# mod_mixer_no_led.net
KiCad netlist of a schematic drawn in EAGLE
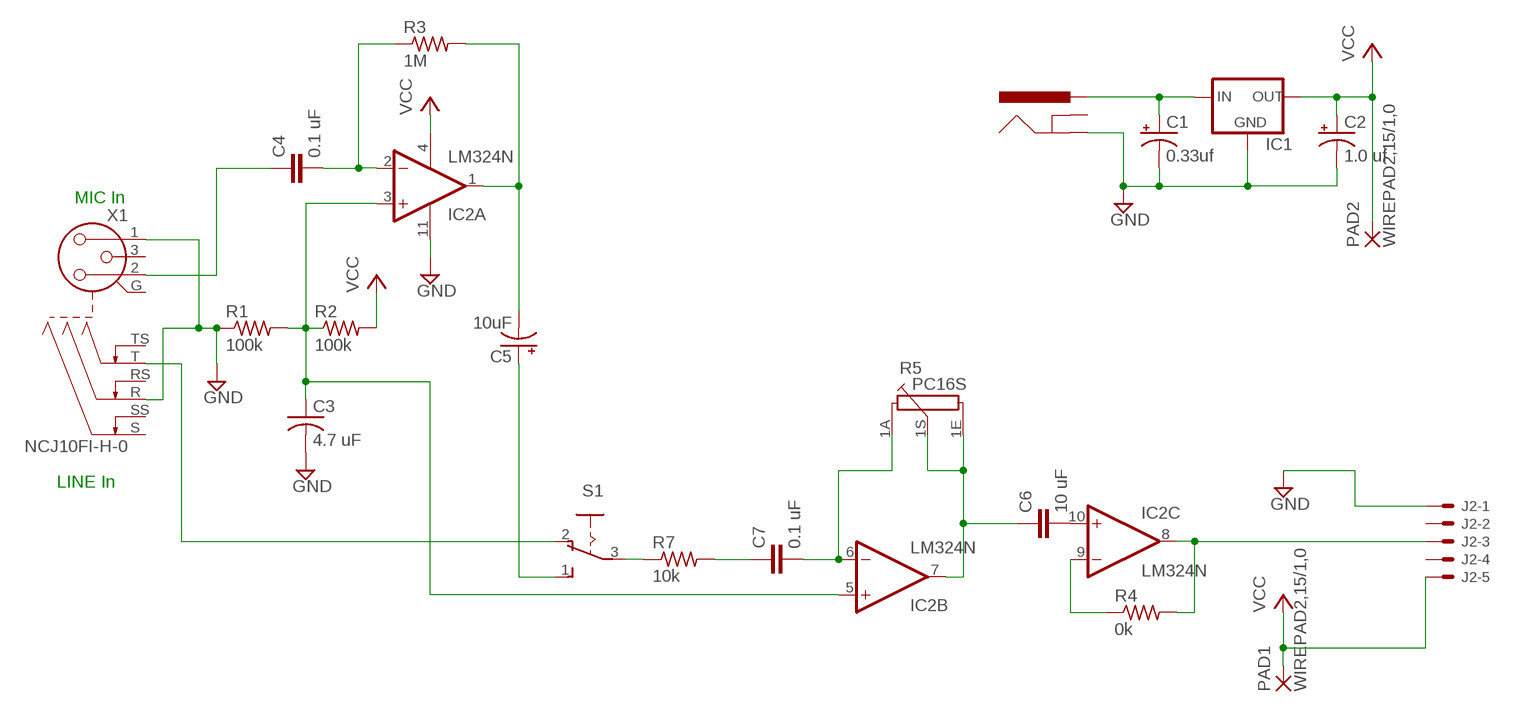
[diagram p0: schematic, sheet 1]

(export (version "E")
  (design (tool "Eeschema 10.0.6"))
  (components
    (comp (ref "C1")
      (value "0.33uf")
      (footprint "eagle-import:E2,5-6")
      (libsource (lib "eagle-import") (part "CPOL-USE2.5-6"))
    )
    (comp (ref "C2")
      (value "1.0 uf")
      (footprint "eagle-import:E2,5-6")
      (libsource (lib "eagle-import") (part "CPOL-USE2.5-6"))
    )
    (comp (ref "C3")
      (value "4.7 uF")
      (footprint "eagle-import:C050-030X075")
      (libsource (lib "eagle-import") (part "C-US050-030X075"))
    )
    (comp (ref "C4")
      (value "0.1 uF")
      (footprint "eagle-import:C5B2.5")
      (libsource (lib "eagle-import") (part "C5/2.5"))
    )
    (comp (ref "C5")
      (value "10uF")
      (footprint "eagle-import:E2,5-7")
      (libsource (lib "eagle-import") (part "CPOL-USE2.5-7"))
    )
    (comp (ref "C6")
      (value "10 uF")
      (footprint "eagle-import:C5B2.5")
      (libsource (lib "eagle-import") (part "C5/2.5"))
    )
    (comp (ref "C7")
      (value "0.1 uF")
      (footprint "eagle-import:C5B2.5")
      (libsource (lib "eagle-import") (part "C5/2.5"))
    )
    (comp (ref "IC1")
      (value "V_REG_78XXSIDE")
      (footprint "eagle-import:78XXL")
      (libsource (lib "eagle-import") (part "V_REG_78XXSIDE"))
    )
    (comp (ref "IC2")
      (value "LM324N")
      (footprint "eagle-import:DIL14")
      (libsource (lib "eagle-import") (part "LM324N"))
    )
    (comp (ref "J1")
      (value "POWER_JACKSLT")
      (footprint "eagle-import:POWER_JACK_SLOT")
      (libsource (lib "eagle-import") (part "POWER_JACKSLT"))
    )
    (comp (ref "J2")
      (value "CON-50-EDGE")
      (footprint "eagle-import:CARDEDGE-50")
      (libsource (lib "eagle-import") (part "CON-50-EDGE"))
    )
    (comp (ref "PAD1")
      (value "WIREPAD2,15/1,0")
      (footprint "eagle-import:2,15_1,0")
      (libsource (lib "eagle-import") (part "WIREPAD2,15/1,0"))
    )
    (comp (ref "PAD2")
      (value "WIREPAD2,15/1,0")
      (footprint "eagle-import:2,15_1,0")
      (libsource (lib "eagle-import") (part "WIREPAD2,15/1,0"))
    )
    (comp (ref "R1")
      (value "100k")
      (footprint "eagle-import:0207_10")
      (libsource (lib "eagle-import") (part "R-US_0207/10"))
    )
    (comp (ref "R2")
      (value "100k")
      (footprint "eagle-import:0207_10")
      (libsource (lib "eagle-import") (part "R-US_0207/10"))
    )
    (comp (ref "R3")
      (value "1M")
      (footprint "eagle-import:0207_10")
      (libsource (lib "eagle-import") (part "R-US_0207/10"))
    )
    (comp (ref "R4")
      (value "0k")
      (footprint "eagle-import:0207_10")
      (libsource (lib "eagle-import") (part "R-US_0207/10"))
    )
    (comp (ref "R5")
      (value "PC16S")
      (footprint "eagle-import:PC16S")
      (libsource (lib "eagle-import") (part "PC16S"))
    )
    (comp (ref "R7")
      (value "10k")
      (footprint "eagle-import:0207_10")
      (libsource (lib "eagle-import") (part "R-US_0207/10"))
    )
    (comp (ref "S1")
      (value "255SB")
      (footprint "eagle-import:255SB")
      (libsource (lib "eagle-import") (part "255SB"))
    )
    (comp (ref "X1")
      (value "NCJ10FI-H-0")
      (footprint "eagle-import:NCJ10FI-H-0")
      (libsource (lib "eagle-import") (part "NCJ10FI-H-0"))
    )
  )
  (nets
    (net (code "1") (name "GND") (class "Default")
      (node (ref "C1") (pin "-") (pinfunction "-_-") (pintype "passive"))
      (node (ref "C2") (pin "-") (pinfunction "-_-") (pintype "passive"))
      (node (ref "C3") (pin "2") (pinfunction "2_2") (pintype "passive"))
      (node (ref "IC1") (pin "GND") (pinfunction "GND_GND") (pintype "input"))
      (node (ref "IC2") (pin "11") (pinfunction "V-_11") (pintype "power_in"))
      (node (ref "J1") (pin "GND@2") (pinfunction "GND_GND@2") (pintype "bidirectional"))
      (node (ref "J2") (pin "1") (pinfunction "S_1") (pintype "passive"))
      (node (ref "R1") (pin "1") (pinfunction "1_1") (pintype "passive"))
      (node (ref "X1") (pin "1") (pinfunction "1_1") (pintype "passive"))
      (node (ref "X1") (pin "R") (pinfunction "R_R") (pintype "passive"))
    )
    (net (code "2") (name "Net-(C1-Pad+)") (class "Default")
      (node (ref "C1") (pin "+") (pinfunction "+_+") (pintype "passive"))
      (node (ref "IC1") (pin "IN") (pinfunction "IN_IN") (pintype "input"))
      (node (ref "J1") (pin "PWR") (pinfunction "PWR_PWR") (pintype "bidirectional"))
    )
    (net (code "3") (name "Net-(C4-Pad1)") (class "Default")
      (node (ref "C4") (pin "1") (pinfunction "1_1") (pintype "passive"))
      (node (ref "X1") (pin "2") (pinfunction "2_2") (pintype "passive"))
    )
    (net (code "4") (name "Net-(C7-Pad1)") (class "Default")
      (node (ref "C7") (pin "1") (pinfunction "1_1") (pintype "passive"))
      (node (ref "R7") (pin "2") (pinfunction "2_2") (pintype "passive"))
    )
    (net (code "5") (name "Net-(IC2A-+IN)") (class "Default")
      (node (ref "C3") (pin "1") (pinfunction "1_1") (pintype "passive"))
      (node (ref "IC2") (pin "3") (pinfunction "+IN_3") (pintype "input"))
      (node (ref "IC2") (pin "5") (pinfunction "+IN_5") (pintype "input"))
      (node (ref "R1") (pin "2") (pinfunction "2_2") (pintype "passive"))
      (node (ref "R2") (pin "1") (pinfunction "1_1") (pintype "passive"))
    )
    (net (code "6") (name "Net-(IC2A--IN)") (class "Default")
      (node (ref "C4") (pin "2") (pinfunction "2_2") (pintype "passive"))
      (node (ref "IC2") (pin "2") (pinfunction "-IN_2") (pintype "input"))
      (node (ref "R3") (pin "1") (pinfunction "1_1") (pintype "passive"))
    )
    (net (code "7") (name "Net-(IC2A-OUT)") (class "Default")
      (node (ref "C5") (pin "-") (pinfunction "-_-") (pintype "passive"))
      (node (ref "IC2") (pin "1") (pinfunction "OUT_1") (pintype "output"))
      (node (ref "R3") (pin "2") (pinfunction "2_2") (pintype "passive"))
    )
    (net (code "8") (name "Net-(IC2B--IN)") (class "Default")
      (node (ref "C7") (pin "2") (pinfunction "2_2") (pintype "passive"))
      (node (ref "IC2") (pin "6") (pinfunction "-IN_6") (pintype "input"))
      (node (ref "R5") (pin "1A") (pinfunction "1A_1A") (pintype "passive"))
    )
    (net (code "9") (name "Net-(IC2B-OUT)") (class "Default")
      (node (ref "C6") (pin "1") (pinfunction "1_1") (pintype "passive"))
      (node (ref "IC2") (pin "7") (pinfunction "OUT_7") (pintype "output"))
      (node (ref "R5") (pin "1E") (pinfunction "1E_1E") (pintype "passive"))
      (node (ref "R5") (pin "1S") (pinfunction "1S_1S") (pintype "passive"))
    )
    (net (code "10") (name "Net-(IC2C-+IN)") (class "Default")
      (node (ref "C6") (pin "2") (pinfunction "2_2") (pintype "passive"))
      (node (ref "IC2") (pin "10") (pinfunction "+IN_10") (pintype "input"))
    )
    (net (code "11") (name "Net-(IC2C--IN)") (class "Default")
      (node (ref "IC2") (pin "9") (pinfunction "-IN_9") (pintype "input"))
      (node (ref "R4") (pin "1") (pinfunction "1_1") (pintype "passive"))
    )
    (net (code "12") (name "Net-(IC2C-OUT)") (class "Default")
      (node (ref "IC2") (pin "8") (pinfunction "OUT_8") (pintype "output"))
      (node (ref "J2") (pin "3") (pinfunction "S_3") (pintype "passive"))
      (node (ref "R4") (pin "2") (pinfunction "2_2") (pintype "passive"))
    )
    (net (code "13") (name "Net-(S1-O)") (class "Default")
      (node (ref "S1") (pin "2") (pinfunction "O_2") (pintype "passive"))
      (node (ref "X1") (pin "T") (pinfunction "T_T") (pintype "passive"))
    )
    (net (code "14") (name "Net-(S1-P)") (class "Default")
      (node (ref "R7") (pin "1") (pinfunction "1_1") (pintype "passive"))
      (node (ref "S1") (pin "3") (pinfunction "P_3") (pintype "passive"))
    )
    (net (code "15") (name "Net-(S1-S)") (class "Default")
      (node (ref "C5") (pin "+") (pinfunction "+_+") (pintype "passive"))
      (node (ref "S1") (pin "1") (pinfunction "S_1") (pintype "passive"))
    )
    (net (code "16") (name "VCC") (class "Default")
      (node (ref "C2") (pin "+") (pinfunction "+_+") (pintype "passive"))
      (node (ref "IC1") (pin "OUT") (pinfunction "OUT_OUT") (pintype "output"))
      (node (ref "IC2") (pin "4") (pinfunction "V+_4") (pintype "power_in"))
      (node (ref "J2") (pin "5") (pinfunction "S_5") (pintype "passive"))
      (node (ref "PAD1") (pin "1") (pinfunction "P_1") (pintype "passive"))
      (node (ref "PAD2") (pin "1") (pinfunction "P_1") (pintype "passive"))
      (node (ref "R2") (pin "2") (pinfunction "2_2") (pintype "passive"))
    )
    (net (code "17") (name "unconnected-(J1-GNDBREAK-PadGND@1)") (class "Default")
      (node (ref "J1") (pin "GND@1") (pinfunction "GNDBREAK_GND@1") (pintype "bidirectional"))
    )
    (net (code "18") (name "unconnected-(J2B-S-Pad2)") (class "Default")
      (node (ref "J2") (pin "2") (pinfunction "S_2") (pintype "passive"))
    )
    (net (code "19") (name "unconnected-(J2D-S-Pad4)") (class "Default")
      (node (ref "J2") (pin "4") (pinfunction "S_4") (pintype "passive"))
    )
    (net (code "20") (name "unconnected-(X1-Pad3)") (class "Default")
      (node (ref "X1") (pin "3") (pinfunction "3_3") (pintype "passive"))
    )
    (net (code "21") (name "unconnected-(X1-PadG)") (class "Default")
      (node (ref "X1") (pin "G") (pinfunction "G_G") (pintype "passive"))
    )
    (net (code "22") (name "unconnected-(X1-PadRS)") (class "Default")
      (node (ref "X1") (pin "RS") (pinfunction "RS_RS") (pintype "passive"))
    )
    (net (code "23") (name "unconnected-(X1-PadS)") (class "Default")
      (node (ref "X1") (pin "S") (pinfunction "S_S") (pintype "passive"))
    )
    (net (code "24") (name "unconnected-(X1-PadSS)") (class "Default")
      (node (ref "X1") (pin "SS") (pinfunction "SS_SS") (pintype "passive"))
    )
    (net (code "25") (name "unconnected-(X1-PadTS)") (class "Default")
      (node (ref "X1") (pin "TS") (pinfunction "TS_TS") (pintype "passive"))
    )
  )
)
